# FPGA_1.net
KiCad netlist of a schematic drawn in Altium Designer
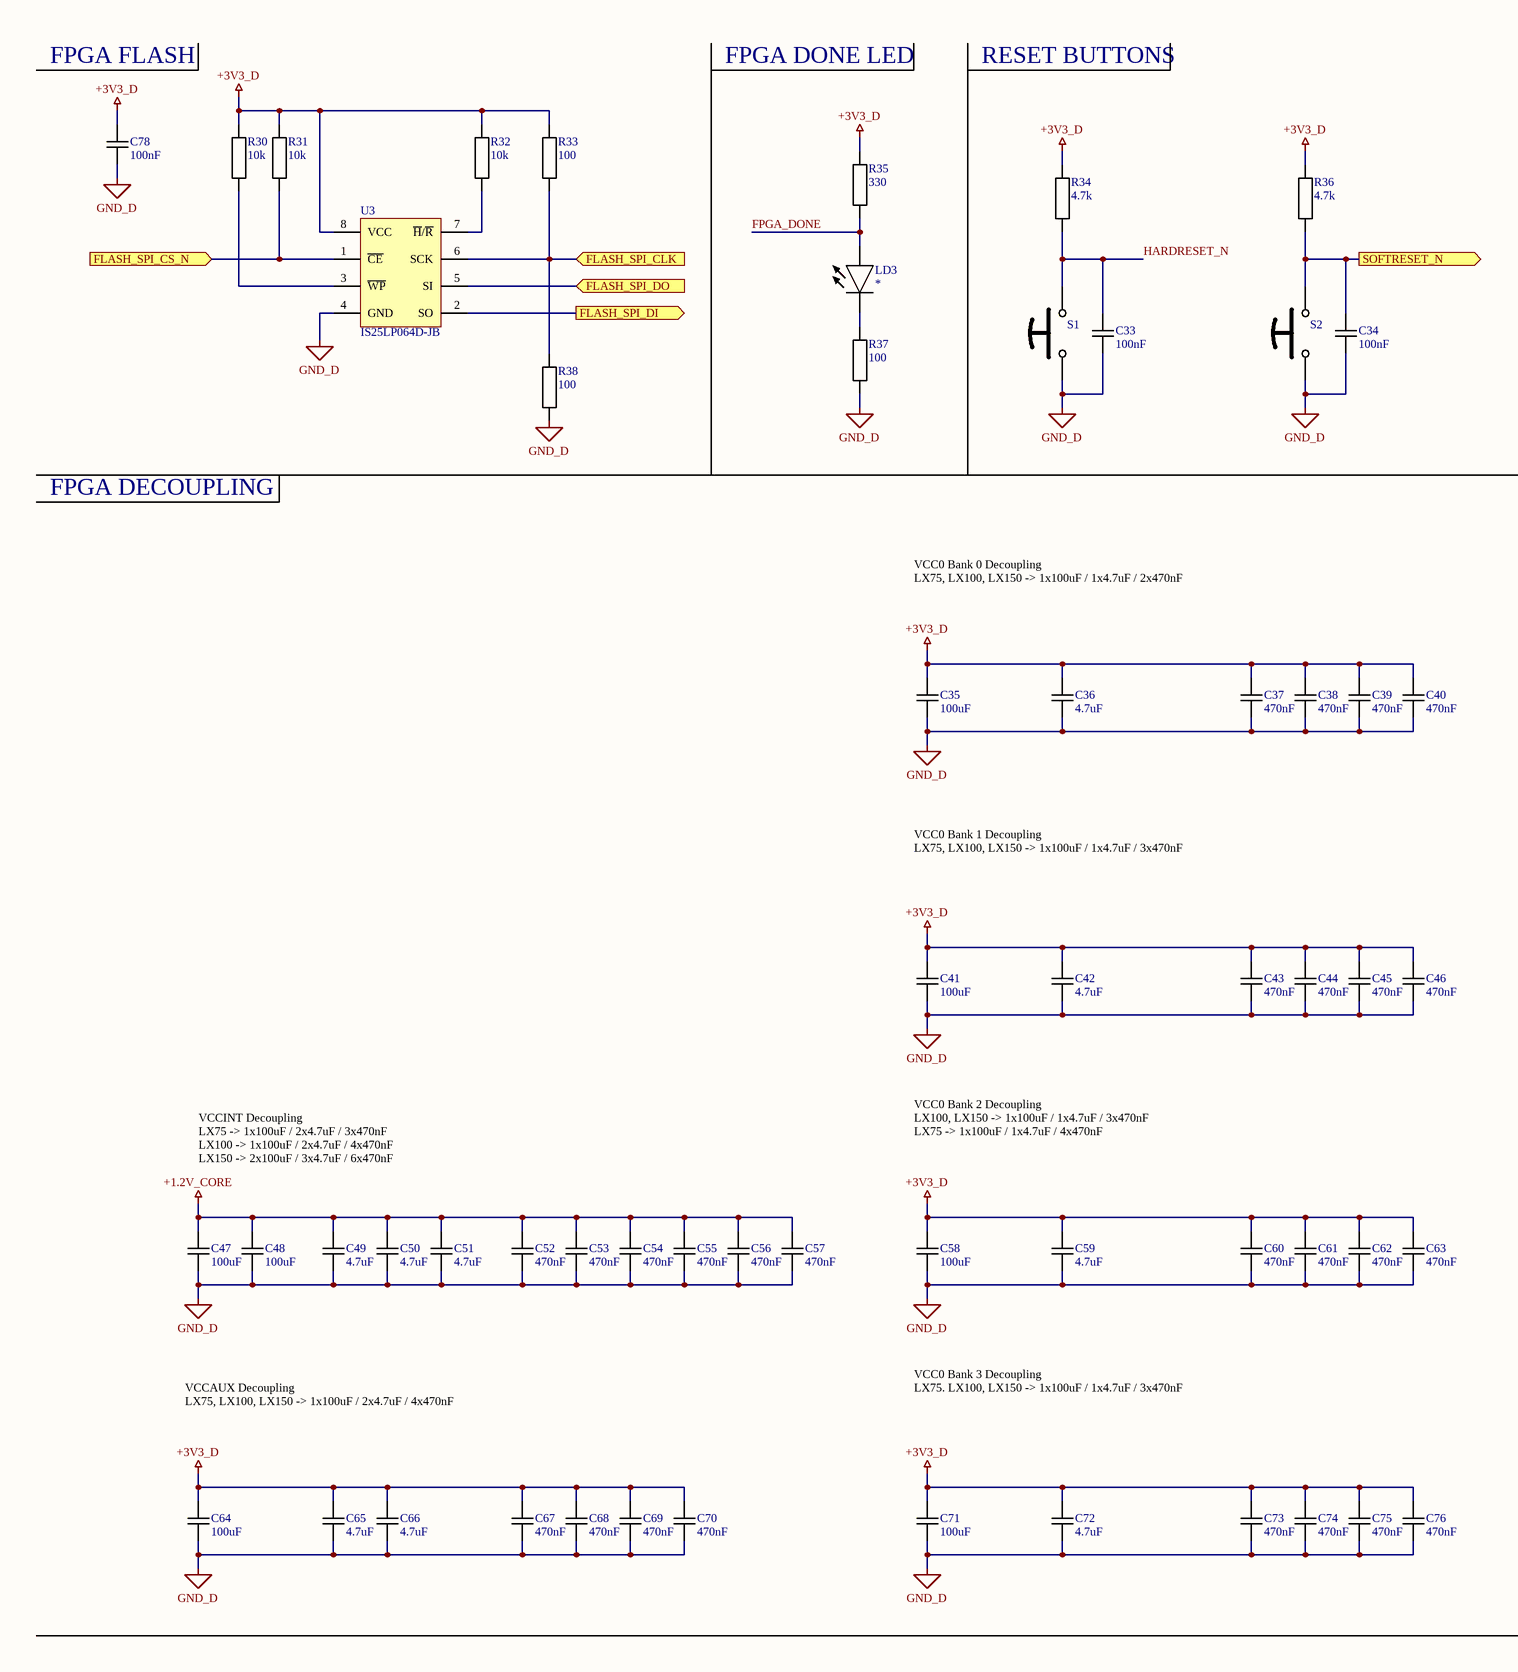
[diagram p0: FPGA_1.SchDoc, left]
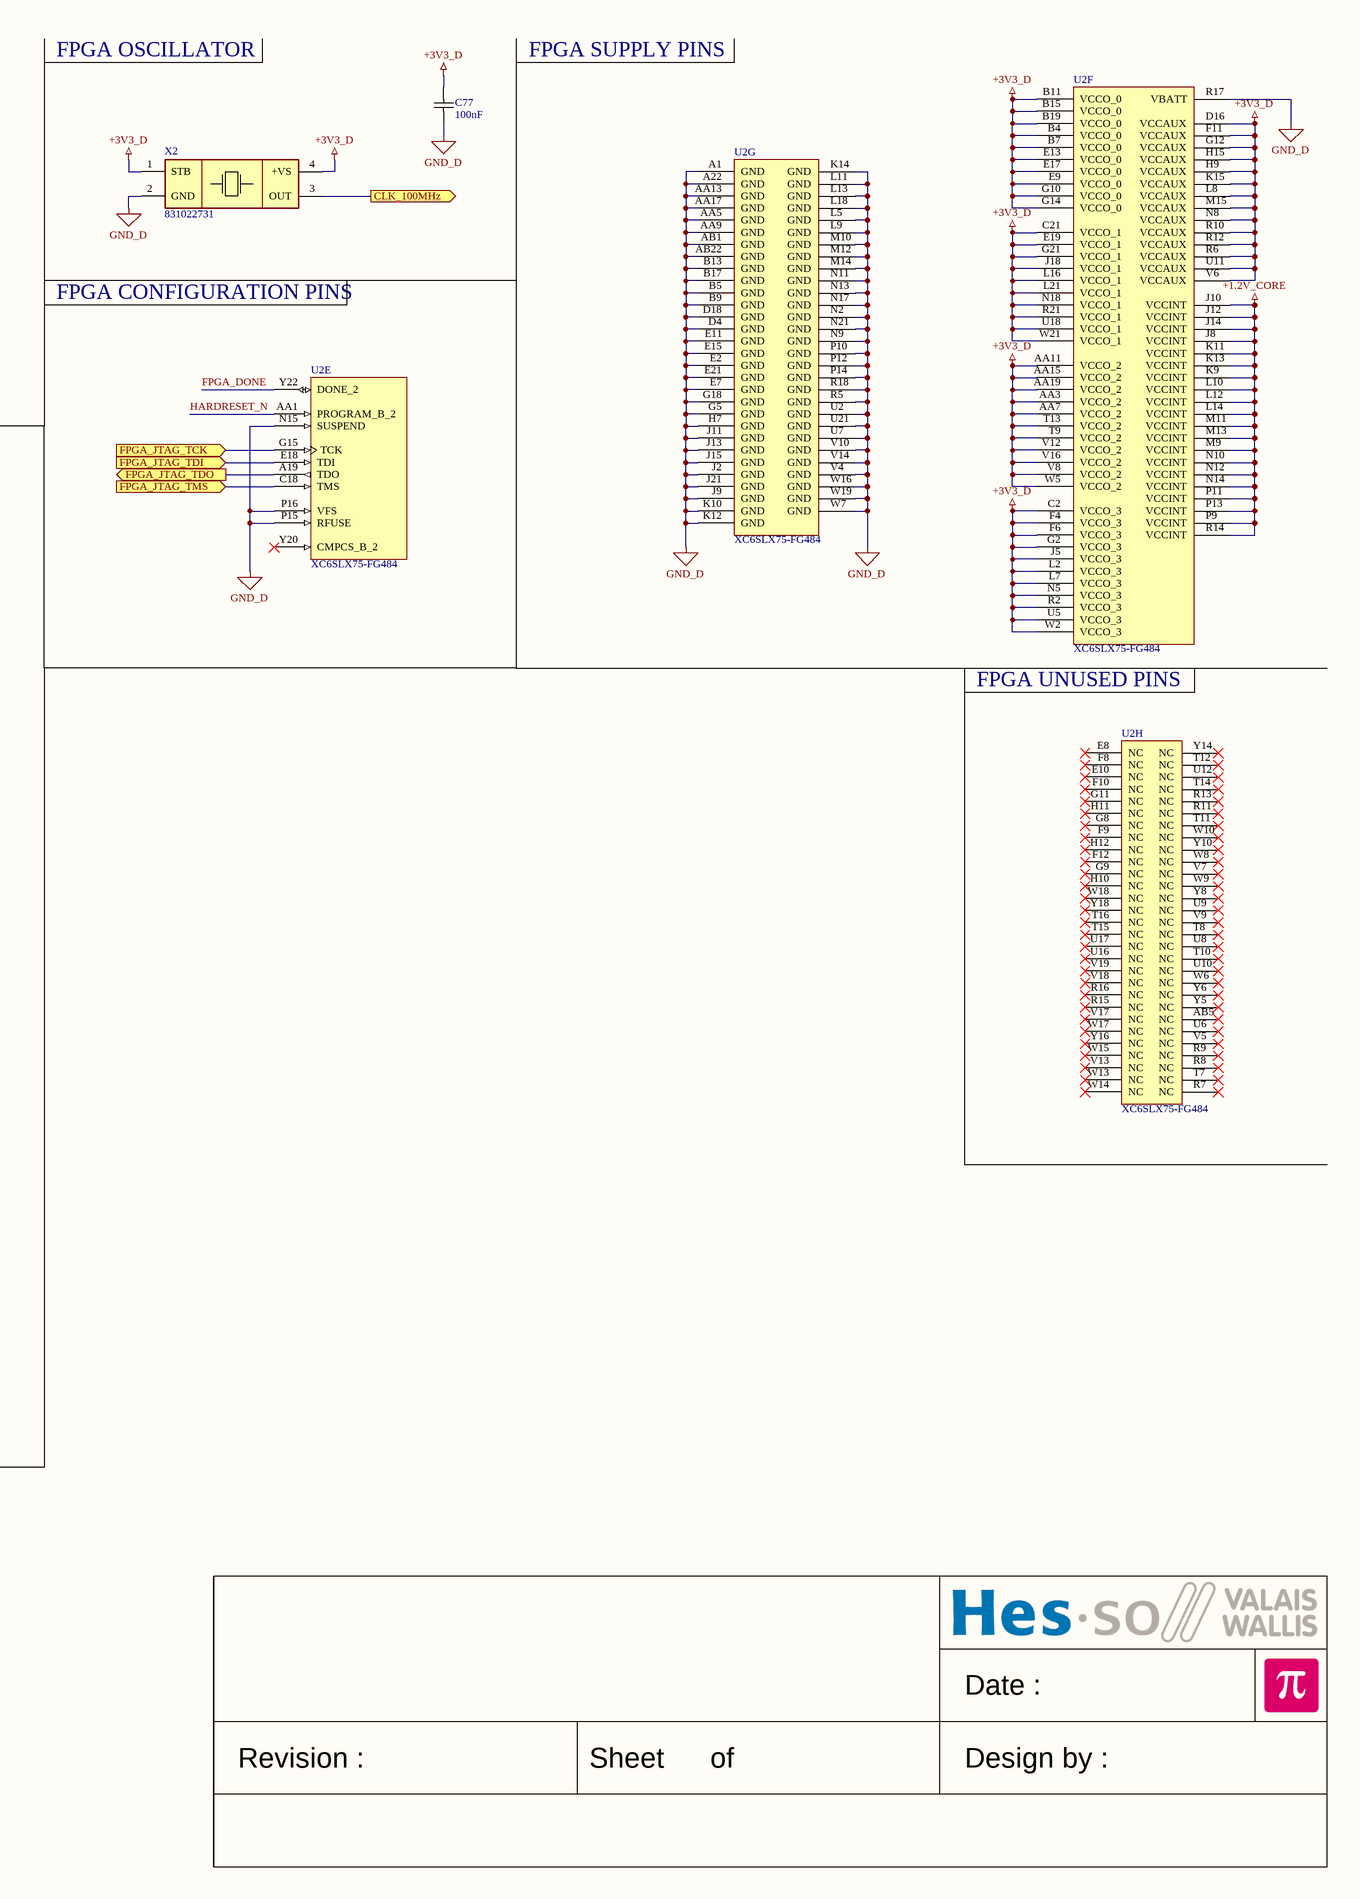
[diagram p1: FPGA_1.SchDoc, right]

(export (version "E")
  (design (tool "Eeschema 10.0.6"))
  (components
    (comp (ref "C33")
      (value "100nF")
      (footprint "CAPACITOR 1608 REFLOW")
      (description "Capacitor")
      (libsource (lib "Capacitor") (part "Capacitor"))
    )
    (comp (ref "C34")
      (value "100nF")
      (footprint "CAPACITOR 1608 REFLOW")
      (description "Capacitor")
      (libsource (lib "Capacitor") (part "Capacitor"))
    )
    (comp (ref "C35")
      (value "100uF")
      (footprint "CAPACITOR 3216 REFLOW")
      (description "Capacitor")
      (libsource (lib "Capacitor") (part "Capacitor"))
    )
    (comp (ref "C36")
      (value "4.7uF")
      (footprint "CAPACITOR 1608 REFLOW")
      (description "Capacitor")
      (libsource (lib "Capacitor") (part "Capacitor"))
    )
    (comp (ref "C37")
      (value "470nF")
      (footprint "CAPACITOR 1005 REFLOW")
      (description "Capacitor")
      (libsource (lib "Capacitor") (part "Capacitor"))
    )
    (comp (ref "C38")
      (value "470nF")
      (footprint "CAPACITOR 1005 REFLOW")
      (description "Capacitor")
      (libsource (lib "Capacitor") (part "Capacitor"))
    )
    (comp (ref "C39")
      (value "470nF")
      (footprint "CAPACITOR 1005 REFLOW")
      (description "Capacitor")
      (libsource (lib "Capacitor") (part "Capacitor"))
    )
    (comp (ref "C40")
      (value "470nF")
      (footprint "CAPACITOR 1005 REFLOW")
      (description "Capacitor")
      (libsource (lib "Capacitor") (part "Capacitor"))
    )
    (comp (ref "C41")
      (value "100uF")
      (footprint "CAPACITOR 3216 REFLOW")
      (description "Capacitor")
      (libsource (lib "Capacitor") (part "Capacitor"))
    )
    (comp (ref "C42")
      (value "4.7uF")
      (footprint "CAPACITOR 1608 REFLOW")
      (description "Capacitor")
      (libsource (lib "Capacitor") (part "Capacitor"))
    )
    (comp (ref "C43")
      (value "470nF")
      (footprint "CAPACITOR 1005 REFLOW")
      (description "Capacitor")
      (libsource (lib "Capacitor") (part "Capacitor"))
    )
    (comp (ref "C44")
      (value "470nF")
      (footprint "CAPACITOR 1005 REFLOW")
      (description "Capacitor")
      (libsource (lib "Capacitor") (part "Capacitor"))
    )
    (comp (ref "C45")
      (value "470nF")
      (footprint "CAPACITOR 1005 REFLOW")
      (description "Capacitor")
      (libsource (lib "Capacitor") (part "Capacitor"))
    )
    (comp (ref "C46")
      (value "470nF")
      (footprint "CAPACITOR 1005 REFLOW")
      (description "Capacitor")
      (libsource (lib "Capacitor") (part "Capacitor"))
    )
    (comp (ref "C47")
      (value "100uF")
      (footprint "CAPACITOR 3216 REFLOW")
      (description "Capacitor")
      (libsource (lib "Capacitor") (part "Capacitor"))
    )
    (comp (ref "C48")
      (value "100uF")
      (footprint "CAPACITOR 3216 REFLOW")
      (description "Capacitor")
      (libsource (lib "Capacitor") (part "Capacitor"))
    )
    (comp (ref "C49")
      (value "4.7uF")
      (footprint "CAPACITOR 1608 REFLOW")
      (description "Capacitor")
      (libsource (lib "Capacitor") (part "Capacitor"))
    )
    (comp (ref "C50")
      (value "4.7uF")
      (footprint "CAPACITOR 1608 REFLOW")
      (description "Capacitor")
      (libsource (lib "Capacitor") (part "Capacitor"))
    )
    (comp (ref "C51")
      (value "4.7uF")
      (footprint "CAPACITOR 1608 REFLOW")
      (description "Capacitor")
      (libsource (lib "Capacitor") (part "Capacitor"))
    )
    (comp (ref "C52")
      (value "470nF")
      (footprint "CAPACITOR 1005 REFLOW")
      (description "Capacitor")
      (libsource (lib "Capacitor") (part "Capacitor"))
    )
    (comp (ref "C53")
      (value "470nF")
      (footprint "CAPACITOR 1005 REFLOW")
      (description "Capacitor")
      (libsource (lib "Capacitor") (part "Capacitor"))
    )
    (comp (ref "C54")
      (value "470nF")
      (footprint "CAPACITOR 1005 REFLOW")
      (description "Capacitor")
      (libsource (lib "Capacitor") (part "Capacitor"))
    )
    (comp (ref "C55")
      (value "470nF")
      (footprint "CAPACITOR 1005 REFLOW")
      (description "Capacitor")
      (libsource (lib "Capacitor") (part "Capacitor"))
    )
    (comp (ref "C56")
      (value "470nF")
      (footprint "CAPACITOR 1005 REFLOW")
      (description "Capacitor")
      (libsource (lib "Capacitor") (part "Capacitor"))
    )
    (comp (ref "C57")
      (value "470nF")
      (footprint "CAPACITOR 1005 REFLOW")
      (description "Capacitor")
      (libsource (lib "Capacitor") (part "Capacitor"))
    )
    (comp (ref "C58")
      (value "100uF")
      (footprint "CAPACITOR 3216 REFLOW")
      (description "Capacitor")
      (libsource (lib "Capacitor") (part "Capacitor"))
    )
    (comp (ref "C59")
      (value "4.7uF")
      (footprint "CAPACITOR 1608 REFLOW")
      (description "Capacitor")
      (libsource (lib "Capacitor") (part "Capacitor"))
    )
    (comp (ref "C60")
      (value "470nF")
      (footprint "CAPACITOR 1005 REFLOW")
      (description "Capacitor")
      (libsource (lib "Capacitor") (part "Capacitor"))
    )
    (comp (ref "C61")
      (value "470nF")
      (footprint "CAPACITOR 1005 REFLOW")
      (description "Capacitor")
      (libsource (lib "Capacitor") (part "Capacitor"))
    )
    (comp (ref "C62")
      (value "470nF")
      (footprint "CAPACITOR 1005 REFLOW")
      (description "Capacitor")
      (libsource (lib "Capacitor") (part "Capacitor"))
    )
    (comp (ref "C63")
      (value "470nF")
      (footprint "CAPACITOR 1005 REFLOW")
      (description "Capacitor")
      (libsource (lib "Capacitor") (part "Capacitor"))
    )
    (comp (ref "C64")
      (value "100uF")
      (footprint "CAPACITOR 3216 REFLOW")
      (description "Capacitor")
      (libsource (lib "Capacitor") (part "Capacitor"))
    )
    (comp (ref "C65")
      (value "4.7uF")
      (footprint "CAPACITOR 1608 REFLOW")
      (description "Capacitor")
      (libsource (lib "Capacitor") (part "Capacitor"))
    )
    (comp (ref "C66")
      (value "4.7uF")
      (footprint "CAPACITOR 1608 REFLOW")
      (description "Capacitor")
      (libsource (lib "Capacitor") (part "Capacitor"))
    )
    (comp (ref "C67")
      (value "470nF")
      (footprint "CAPACITOR 1005 REFLOW")
      (description "Capacitor")
      (libsource (lib "Capacitor") (part "Capacitor"))
    )
    (comp (ref "C68")
      (value "470nF")
      (footprint "CAPACITOR 1005 REFLOW")
      (description "Capacitor")
      (libsource (lib "Capacitor") (part "Capacitor"))
    )
    (comp (ref "C69")
      (value "470nF")
      (footprint "CAPACITOR 1005 REFLOW")
      (description "Capacitor")
      (libsource (lib "Capacitor") (part "Capacitor"))
    )
    (comp (ref "C70")
      (value "470nF")
      (footprint "CAPACITOR 1005 REFLOW")
      (description "Capacitor")
      (libsource (lib "Capacitor") (part "Capacitor"))
    )
    (comp (ref "C71")
      (value "100uF")
      (footprint "CAPACITOR 3216 REFLOW")
      (description "Capacitor")
      (libsource (lib "Capacitor") (part "Capacitor"))
    )
    (comp (ref "C72")
      (value "4.7uF")
      (footprint "CAPACITOR 1608 REFLOW")
      (description "Capacitor")
      (libsource (lib "Capacitor") (part "Capacitor"))
    )
    (comp (ref "C73")
      (value "470nF")
      (footprint "CAPACITOR 1005 REFLOW")
      (description "Capacitor")
      (libsource (lib "Capacitor") (part "Capacitor"))
    )
    (comp (ref "C74")
      (value "470nF")
      (footprint "CAPACITOR 1005 REFLOW")
      (description "Capacitor")
      (libsource (lib "Capacitor") (part "Capacitor"))
    )
    (comp (ref "C75")
      (value "470nF")
      (footprint "CAPACITOR 1005 REFLOW")
      (description "Capacitor")
      (libsource (lib "Capacitor") (part "Capacitor"))
    )
    (comp (ref "C76")
      (value "470nF")
      (footprint "CAPACITOR 1005 REFLOW")
      (description "Capacitor")
      (libsource (lib "Capacitor") (part "Capacitor"))
    )
    (comp (ref "C77")
      (value "100nF")
      (footprint "CAPACITOR 1608 REFLOW")
      (description "Capacitor")
      (libsource (lib "Capacitor") (part "Capacitor"))
    )
    (comp (ref "C78")
      (value "100nF")
      (footprint "CAPACITOR 1608 REFLOW")
      (description "Capacitor")
      (libsource (lib "Capacitor") (part "Capacitor"))
    )
    (comp (ref "LD3")
      (value "*")
      (footprint "LED 1608 REFLOW")
      (description "LED generic")
      (libsource (lib "Diode") (part "LED"))
    )
    (comp (ref "R30")
      (value "10k")
      (footprint "RESISTOR 1608 REFLOW")
      (description "Resistor 1% 50V 100mW 1608(0603)")
      (libsource (lib "Resistor") (part "Resistor"))
    )
    (comp (ref "R31")
      (value "10k")
      (footprint "RESISTOR 1608 REFLOW")
      (description "Resistor 1% 50V 100mW 1608(0603)")
      (libsource (lib "Resistor") (part "Resistor"))
    )
    (comp (ref "R32")
      (value "10k")
      (footprint "RESISTOR 1608 REFLOW")
      (description "Resistor 1% 50V 100mW 1608(0603)")
      (libsource (lib "Resistor") (part "Resistor"))
    )
    (comp (ref "R33")
      (value "100")
      (footprint "RESISTOR 1608 REFLOW")
      (description "Resistor 1% 50V 100mW 1608(0603)")
      (libsource (lib "Resistor") (part "Resistor"))
    )
    (comp (ref "R34")
      (value "4.7k")
      (footprint "RESISTOR 1608 REFLOW")
      (description "Resistor 1% 50V 125mW 2012(0805)")
      (libsource (lib "Resistor") (part "Resistor"))
    )
    (comp (ref "R35")
      (value "330")
      (footprint "RESISTOR 1608 REFLOW")
      (description "Resistor 1% 50V 125mW 2012(0805)")
      (libsource (lib "Resistor") (part "Resistor"))
    )
    (comp (ref "R36")
      (value "4.7k")
      (footprint "RESISTOR 1608 REFLOW")
      (description "Resistor 1% 50V 125mW 2012(0805)")
      (libsource (lib "Resistor") (part "Resistor"))
    )
    (comp (ref "R37")
      (value "100")
      (footprint "RESISTOR 1608 REFLOW")
      (description "Resistor 1% 50V 125mW 2012(0805)")
      (libsource (lib "Resistor") (part "Resistor"))
    )
    (comp (ref "R38")
      (value "100")
      (footprint "RESISTOR 1608 REFLOW")
      (description "Resistor 1% 50V 100mW 1608(0603)")
      (libsource (lib "Resistor") (part "Resistor"))
    )
    (comp (ref "S1")
      (value "*")
      (footprint "Push Button C6.0x3.5 Tyco FSMSM")
      (description "Push Button, 2 pins")
      (libsource (lib "Button") (part "Push Button 2Pins"))
    )
    (comp (ref "S2")
      (value "*")
      (footprint "Push Button C6.0x3.5 Tyco FSMSM")
      (description "Push Button, 2 pins")
      (libsource (lib "Button") (part "Push Button 2Pins"))
    )
    (comp (ref "U2")
      (value "XC6SLX75-FG484")
      (footprint "BGA484 P1.0 C23X23 H2.2")
      (description "Spartan-6 LXT 1.2V FPGA, 268 User I/Os, 484-Ball Fine-Pitch BGA (1.0mm Pitch)")
      (libsource (lib "Processor") (part "XC6SLX75-FG484"))
    )
    (comp (ref "U3")
      (value "IS25LP064D-JB")
      (footprint "SO8 P1.27 C4.0X5.0 H1.75")
      (description "64Mb Serial Flash Memory")
      (libsource (lib "Memory") (part "IS25LP064D-JB"))
    )
    (comp (ref "X2")
      (value "831022731")
      (footprint "Oscillator C5.2x7.2 IQD LFSPXO")
      (description "Oscillator C5.2x7.2 IQD LFSPXO")
      (libsource (lib "Oscillator") (part "Oscillator C5.2x7.2 IQD LFSPXO"))
    )
  )
  (nets
    (net (code "1") (name "+1.2V_CORE") (class "Default")
      (node (ref "C47") (pin "1") (pinfunction "1_1") (pintype "passive"))
      (node (ref "C48") (pin "1") (pinfunction "1_1") (pintype "passive"))
      (node (ref "C49") (pin "1") (pinfunction "1_1") (pintype "passive"))
      (node (ref "C50") (pin "1") (pinfunction "1_1") (pintype "passive"))
      (node (ref "C51") (pin "1") (pinfunction "1_1") (pintype "passive"))
      (node (ref "C52") (pin "1") (pinfunction "1_1") (pintype "passive"))
      (node (ref "C53") (pin "1") (pinfunction "1_1") (pintype "passive"))
      (node (ref "C54") (pin "1") (pinfunction "1_1") (pintype "passive"))
      (node (ref "C55") (pin "1") (pinfunction "1_1") (pintype "passive"))
      (node (ref "C56") (pin "1") (pinfunction "1_1") (pintype "passive"))
      (node (ref "C57") (pin "1") (pinfunction "1_1") (pintype "passive"))
      (node (ref "U2") (pin "J10") (pinfunction "VCCINT_J10") (pintype "power_in"))
      (node (ref "U2") (pin "J12") (pinfunction "VCCINT_J12") (pintype "power_in"))
      (node (ref "U2") (pin "J14") (pinfunction "VCCINT_J14") (pintype "power_in"))
      (node (ref "U2") (pin "J8") (pinfunction "VCCINT_J8") (pintype "power_in"))
      (node (ref "U2") (pin "K11") (pinfunction "VCCINT_K11") (pintype "power_in"))
      (node (ref "U2") (pin "K13") (pinfunction "VCCINT_K13") (pintype "power_in"))
      (node (ref "U2") (pin "K9") (pinfunction "VCCINT_K9") (pintype "power_in"))
      (node (ref "U2") (pin "L10") (pinfunction "VCCINT_L10") (pintype "power_in"))
      (node (ref "U2") (pin "L12") (pinfunction "VCCINT_L12") (pintype "power_in"))
      (node (ref "U2") (pin "L14") (pinfunction "VCCINT_L14") (pintype "power_in"))
      (node (ref "U2") (pin "M11") (pinfunction "VCCINT_M11") (pintype "power_in"))
      (node (ref "U2") (pin "M13") (pinfunction "VCCINT_M13") (pintype "power_in"))
      (node (ref "U2") (pin "M9") (pinfunction "VCCINT_M9") (pintype "power_in"))
      (node (ref "U2") (pin "N10") (pinfunction "VCCINT_N10") (pintype "power_in"))
      (node (ref "U2") (pin "N12") (pinfunction "VCCINT_N12") (pintype "power_in"))
      (node (ref "U2") (pin "N14") (pinfunction "VCCINT_N14") (pintype "power_in"))
      (node (ref "U2") (pin "P11") (pinfunction "VCCINT_P11") (pintype "power_in"))
      (node (ref "U2") (pin "P13") (pinfunction "VCCINT_P13") (pintype "power_in"))
      (node (ref "U2") (pin "P9") (pinfunction "VCCINT_P9") (pintype "power_in"))
      (node (ref "U2") (pin "R14") (pinfunction "VCCINT_R14") (pintype "power_in"))
    )
    (net (code "2") (name "+3V3_D") (class "Default")
      (node (ref "C35") (pin "1") (pinfunction "1_1") (pintype "passive"))
      (node (ref "C36") (pin "1") (pinfunction "1_1") (pintype "passive"))
      (node (ref "C37") (pin "1") (pinfunction "1_1") (pintype "passive"))
      (node (ref "C38") (pin "1") (pinfunction "1_1") (pintype "passive"))
      (node (ref "C39") (pin "1") (pinfunction "1_1") (pintype "passive"))
      (node (ref "C40") (pin "1") (pinfunction "1_1") (pintype "passive"))
      (node (ref "C41") (pin "1") (pinfunction "1_1") (pintype "passive"))
      (node (ref "C42") (pin "1") (pinfunction "1_1") (pintype "passive"))
      (node (ref "C43") (pin "1") (pinfunction "1_1") (pintype "passive"))
      (node (ref "C44") (pin "1") (pinfunction "1_1") (pintype "passive"))
      (node (ref "C45") (pin "1") (pinfunction "1_1") (pintype "passive"))
      (node (ref "C46") (pin "1") (pinfunction "1_1") (pintype "passive"))
      (node (ref "C58") (pin "1") (pinfunction "1_1") (pintype "passive"))
      (node (ref "C59") (pin "1") (pinfunction "1_1") (pintype "passive"))
      (node (ref "C60") (pin "1") (pinfunction "1_1") (pintype "passive"))
      (node (ref "C61") (pin "1") (pinfunction "1_1") (pintype "passive"))
      (node (ref "C62") (pin "1") (pinfunction "1_1") (pintype "passive"))
      (node (ref "C63") (pin "1") (pinfunction "1_1") (pintype "passive"))
      (node (ref "C64") (pin "1") (pinfunction "1_1") (pintype "passive"))
      (node (ref "C65") (pin "1") (pinfunction "1_1") (pintype "passive"))
      (node (ref "C66") (pin "1") (pinfunction "1_1") (pintype "passive"))
      (node (ref "C67") (pin "1") (pinfunction "1_1") (pintype "passive"))
      (node (ref "C68") (pin "1") (pinfunction "1_1") (pintype "passive"))
      (node (ref "C69") (pin "1") (pinfunction "1_1") (pintype "passive"))
      (node (ref "C70") (pin "1") (pinfunction "1_1") (pintype "passive"))
      (node (ref "C71") (pin "1") (pinfunction "1_1") (pintype "passive"))
      (node (ref "C72") (pin "1") (pinfunction "1_1") (pintype "passive"))
      (node (ref "C73") (pin "1") (pinfunction "1_1") (pintype "passive"))
      (node (ref "C74") (pin "1") (pinfunction "1_1") (pintype "passive"))
      (node (ref "C75") (pin "1") (pinfunction "1_1") (pintype "passive"))
      (node (ref "C76") (pin "1") (pinfunction "1_1") (pintype "passive"))
      (node (ref "C77") (pin "2") (pinfunction "2_2") (pintype "passive"))
      (node (ref "C78") (pin "2") (pinfunction "2_2") (pintype "passive"))
      (node (ref "R30") (pin "2") (pinfunction "2_2") (pintype "passive"))
      (node (ref "R31") (pin "2") (pinfunction "2_2") (pintype "passive"))
      (node (ref "R32") (pin "2") (pinfunction "2_2") (pintype "passive"))
      (node (ref "R33") (pin "2") (pinfunction "2_2") (pintype "passive"))
      (node (ref "R34") (pin "2") (pinfunction "2_2") (pintype "passive"))
      (node (ref "R35") (pin "2") (pinfunction "2_2") (pintype "passive"))
      (node (ref "R36") (pin "2") (pinfunction "2_2") (pintype "passive"))
      (node (ref "U2") (pin "AA11") (pinfunction "VCCO_2_AA11") (pintype "power_in"))
      (node (ref "U2") (pin "AA15") (pinfunction "VCCO_2_AA15") (pintype "power_in"))
      (node (ref "U2") (pin "AA19") (pinfunction "VCCO_2_AA19") (pintype "power_in"))
      (node (ref "U2") (pin "AA3") (pinfunction "VCCO_2_AA3") (pintype "power_in"))
      (node (ref "U2") (pin "AA7") (pinfunction "VCCO_2_AA7") (pintype "power_in"))
      (node (ref "U2") (pin "B11") (pinfunction "VCCO_0_B11") (pintype "power_in"))
      (node (ref "U2") (pin "B15") (pinfunction "VCCO_0_B15") (pintype "power_in"))
      (node (ref "U2") (pin "B19") (pinfunction "VCCO_0_B19") (pintype "power_in"))
      (node (ref "U2") (pin "B4") (pinfunction "VCCO_0_B4") (pintype "power_in"))
      (node (ref "U2") (pin "B7") (pinfunction "VCCO_0_B7") (pintype "power_in"))
      (node (ref "U2") (pin "C2") (pinfunction "VCCO_3_C2") (pintype "power_in"))
      (node (ref "U2") (pin "C21") (pinfunction "VCCO_1_C21") (pintype "power_in"))
      (node (ref "U2") (pin "D16") (pinfunction "VCCAUX_D16") (pintype "power_in"))
      (node (ref "U2") (pin "E13") (pinfunction "VCCO_0_E13") (pintype "power_in"))
      (node (ref "U2") (pin "E17") (pinfunction "VCCO_0_E17") (pintype "power_in"))
      (node (ref "U2") (pin "E19") (pinfunction "VCCO_1_E19") (pintype "power_in"))
      (node (ref "U2") (pin "E9") (pinfunction "VCCO_0_E9") (pintype "power_in"))
      (node (ref "U2") (pin "F11") (pinfunction "VCCAUX_F11") (pintype "power_in"))
      (node (ref "U2") (pin "F4") (pinfunction "VCCO_3_F4") (pintype "power_in"))
      (node (ref "U2") (pin "F6") (pinfunction "VCCO_3_F6") (pintype "power_in"))
      (node (ref "U2") (pin "G10") (pinfunction "VCCO_0_G10") (pintype "power_in"))
      (node (ref "U2") (pin "G12") (pinfunction "VCCAUX_G12") (pintype "power_in"))
      (node (ref "U2") (pin "G14") (pinfunction "VCCO_0_G14") (pintype "power_in"))
      (node (ref "U2") (pin "G2") (pinfunction "VCCO_3_G2") (pintype "power_in"))
      (node (ref "U2") (pin "G21") (pinfunction "VCCO_1_G21") (pintype "power_in"))
      (node (ref "U2") (pin "H15") (pinfunction "VCCAUX_H15") (pintype "power_in"))
      (node (ref "U2") (pin "H9") (pinfunction "VCCAUX_H9") (pintype "power_in"))
      (node (ref "U2") (pin "J18") (pinfunction "VCCO_1_J18") (pintype "power_in"))
      (node (ref "U2") (pin "J5") (pinfunction "VCCO_3_J5") (pintype "power_in"))
      (node (ref "U2") (pin "K15") (pinfunction "VCCAUX_K15") (pintype "power_in"))
      (node (ref "U2") (pin "L16") (pinfunction "VCCO_1_L16") (pintype "power_in"))
      (node (ref "U2") (pin "L2") (pinfunction "VCCO_3_L2") (pintype "power_in"))
      (node (ref "U2") (pin "L21") (pinfunction "VCCO_1_L21") (pintype "power_in"))
      (node (ref "U2") (pin "L7") (pinfunction "VCCO_3_L7") (pintype "power_in"))
      (node (ref "U2") (pin "L8") (pinfunction "VCCAUX_L8") (pintype "power_in"))
      (node (ref "U2") (pin "M15") (pinfunction "VCCAUX_M15") (pintype "power_in"))
      (node (ref "U2") (pin "N18") (pinfunction "VCCO_1_N18") (pintype "power_in"))
      (node (ref "U2") (pin "N5") (pinfunction "VCCO_3_N5") (pintype "power_in"))
      (node (ref "U2") (pin "N8") (pinfunction "VCCAUX_N8") (pintype "power_in"))
      (node (ref "U2") (pin "R10") (pinfunction "VCCAUX_R10") (pintype "power_in"))
      (node (ref "U2") (pin "R12") (pinfunction "VCCAUX_R12") (pintype "power_in"))
      (node (ref "U2") (pin "R2") (pinfunction "VCCO_3_R2") (pintype "power_in"))
      (node (ref "U2") (pin "R21") (pinfunction "VCCO_1_R21") (pintype "power_in"))
      (node (ref "U2") (pin "R6") (pinfunction "VCCAUX_R6") (pintype "power_in"))
      (node (ref "U2") (pin "T13") (pinfunction "VCCO_2_T13") (pintype "power_in"))
      (node (ref "U2") (pin "T9") (pinfunction "VCCO_2_T9") (pintype "power_in"))
      (node (ref "U2") (pin "U11") (pinfunction "VCCAUX_U11") (pintype "power_in"))
      (node (ref "U2") (pin "U18") (pinfunction "VCCO_1_U18") (pintype "power_in"))
      (node (ref "U2") (pin "U5") (pinfunction "VCCO_3_U5") (pintype "power_in"))
      (node (ref "U2") (pin "V12") (pinfunction "VCCO_2_V12") (pintype "power_in"))
      (node (ref "U2") (pin "V16") (pinfunction "VCCO_2_V16") (pintype "power_in"))
      (node (ref "U2") (pin "V6") (pinfunction "VCCAUX_V6") (pintype "power_in"))
      (node (ref "U2") (pin "V8") (pinfunction "VCCO_2_V8") (pintype "power_in"))
      (node (ref "U2") (pin "W2") (pinfunction "VCCO_3_W2") (pintype "power_in"))
      (node (ref "U2") (pin "W21") (pinfunction "VCCO_1_W21") (pintype "power_in"))
      (node (ref "U2") (pin "W5") (pinfunction "VCCO_2_W5") (pintype "power_in"))
      (node (ref "U3") (pin "8") (pinfunction "VCC_8") (pintype "power_in"))
      (node (ref "X2") (pin "1") (pinfunction "STB_1") (pintype "passive"))
      (node (ref "X2") (pin "4") (pinfunction "+VS_4") (pintype "passive"))
    )
    (net (code "3") (name "/CLK_100MHz") (class "Default")
      (node (ref "X2") (pin "3") (pinfunction "OUT_3") (pintype "passive"))
    )
    (net (code "4") (name "/FLASH_SPI_CLK") (class "Default")
      (node (ref "R33") (pin "1") (pinfunction "1_1") (pintype "passive"))
      (node (ref "R38") (pin "2") (pinfunction "2_2") (pintype "passive"))
      (node (ref "U3") (pin "6") (pinfunction "SCK_6") (pintype "passive"))
    )
    (net (code "5") (name "/FLASH_SPI_CS_N") (class "Default")
      (node (ref "R31") (pin "1") (pinfunction "1_1") (pintype "passive"))
      (node (ref "U3") (pin "1") (pinfunction "~{CE}_1") (pintype "passive"))
    )
    (net (code "6") (name "/FLASH_SPI_DI") (class "Default")
      (node (ref "U3") (pin "2") (pinfunction "SO_2") (pintype "passive"))
    )
    (net (code "7") (name "/FLASH_SPI_DO") (class "Default")
      (node (ref "U3") (pin "5") (pinfunction "SI_5") (pintype "passive"))
    )
    (net (code "8") (name "/FPGA_DONE") (class "Default")
      (node (ref "LD3") (pin "2") (pinfunction "A_2") (pintype "passive"))
      (node (ref "R35") (pin "1") (pinfunction "1_1") (pintype "passive"))
      (node (ref "U2") (pin "Y22") (pinfunction "DONE_2_Y22") (pintype "bidirectional"))
    )
    (net (code "9") (name "/FPGA_JTAG_TCK") (class "Default")
      (node (ref "U2") (pin "G15") (pinfunction "TCK_G15") (pintype "input"))
    )
    (net (code "10") (name "/FPGA_JTAG_TDI") (class "Default")
      (node (ref "U2") (pin "E18") (pinfunction "TDI_E18") (pintype "input"))
    )
    (net (code "11") (name "/FPGA_JTAG_TDO") (class "Default")
      (node (ref "U2") (pin "A19") (pinfunction "TDO_A19") (pintype "output"))
    )
    (net (code "12") (name "/FPGA_JTAG_TMS") (class "Default")
      (node (ref "U2") (pin "C18") (pinfunction "TMS_C18") (pintype "input"))
    )
    (net (code "13") (name "/HARDRESET_N") (class "Default")
      (node (ref "C33") (pin "2") (pinfunction "2_2") (pintype "passive"))
      (node (ref "R34") (pin "1") (pinfunction "1_1") (pintype "passive"))
      (node (ref "S1") (pin "2") (pinfunction "2_2") (pintype "passive"))
      (node (ref "U2") (pin "AA1") (pinfunction "PROGRAM_B_2_AA1") (pintype "input"))
    )
    (net (code "14") (name "/SOFTRESET_N") (class "Default")
      (node (ref "C34") (pin "2") (pinfunction "2_2") (pintype "passive"))
      (node (ref "R36") (pin "1") (pinfunction "1_1") (pintype "passive"))
      (node (ref "S2") (pin "2") (pinfunction "2_2") (pintype "passive"))
    )
    (net (code "15") (name "GND_D") (class "Default")
      (node (ref "C33") (pin "1") (pinfunction "1_1") (pintype "passive"))
      (node (ref "C34") (pin "1") (pinfunction "1_1") (pintype "passive"))
      (node (ref "C35") (pin "2") (pinfunction "2_2") (pintype "passive"))
      (node (ref "C36") (pin "2") (pinfunction "2_2") (pintype "passive"))
      (node (ref "C37") (pin "2") (pinfunction "2_2") (pintype "passive"))
      (node (ref "C38") (pin "2") (pinfunction "2_2") (pintype "passive"))
      (node (ref "C39") (pin "2") (pinfunction "2_2") (pintype "passive"))
      (node (ref "C40") (pin "2") (pinfunction "2_2") (pintype "passive"))
      (node (ref "C41") (pin "2") (pinfunction "2_2") (pintype "passive"))
      (node (ref "C42") (pin "2") (pinfunction "2_2") (pintype "passive"))
      (node (ref "C43") (pin "2") (pinfunction "2_2") (pintype "passive"))
      (node (ref "C44") (pin "2") (pinfunction "2_2") (pintype "passive"))
      (node (ref "C45") (pin "2") (pinfunction "2_2") (pintype "passive"))
      (node (ref "C46") (pin "2") (pinfunction "2_2") (pintype "passive"))
      (node (ref "C47") (pin "2") (pinfunction "2_2") (pintype "passive"))
      (node (ref "C48") (pin "2") (pinfunction "2_2") (pintype "passive"))
      (node (ref "C49") (pin "2") (pinfunction "2_2") (pintype "passive"))
      (node (ref "C50") (pin "2") (pinfunction "2_2") (pintype "passive"))
      (node (ref "C51") (pin "2") (pinfunction "2_2") (pintype "passive"))
      (node (ref "C52") (pin "2") (pinfunction "2_2") (pintype "passive"))
      (node (ref "C53") (pin "2") (pinfunction "2_2") (pintype "passive"))
      (node (ref "C54") (pin "2") (pinfunction "2_2") (pintype "passive"))
      (node (ref "C55") (pin "2") (pinfunction "2_2") (pintype "passive"))
      (node (ref "C56") (pin "2") (pinfunction "2_2") (pintype "passive"))
      (node (ref "C57") (pin "2") (pinfunction "2_2") (pintype "passive"))
      (node (ref "C58") (pin "2") (pinfunction "2_2") (pintype "passive"))
      (node (ref "C59") (pin "2") (pinfunction "2_2") (pintype "passive"))
      (node (ref "C60") (pin "2") (pinfunction "2_2") (pintype "passive"))
      (node (ref "C61") (pin "2") (pinfunction "2_2") (pintype "passive"))
      (node (ref "C62") (pin "2") (pinfunction "2_2") (pintype "passive"))
      (node (ref "C63") (pin "2") (pinfunction "2_2") (pintype "passive"))
      (node (ref "C64") (pin "2") (pinfunction "2_2") (pintype "passive"))
      (node (ref "C65") (pin "2") (pinfunction "2_2") (pintype "passive"))
      (node (ref "C66") (pin "2") (pinfunction "2_2") (pintype "passive"))
      (node (ref "C67") (pin "2") (pinfunction "2_2") (pintype "passive"))
      (node (ref "C68") (pin "2") (pinfunction "2_2") (pintype "passive"))
      (node (ref "C69") (pin "2") (pinfunction "2_2") (pintype "passive"))
      (node (ref "C70") (pin "2") (pinfunction "2_2") (pintype "passive"))
      (node (ref "C71") (pin "2") (pinfunction "2_2") (pintype "passive"))
      (node (ref "C72") (pin "2") (pinfunction "2_2") (pintype "passive"))
      (node (ref "C73") (pin "2") (pinfunction "2_2") (pintype "passive"))
      (node (ref "C74") (pin "2") (pinfunction "2_2") (pintype "passive"))
      (node (ref "C75") (pin "2") (pinfunction "2_2") (pintype "passive"))
      (node (ref "C76") (pin "2") (pinfunction "2_2") (pintype "passive"))
      (node (ref "C77") (pin "1") (pinfunction "1_1") (pintype "passive"))
      (node (ref "C78") (pin "1") (pinfunction "1_1") (pintype "passive"))
      (node (ref "R37") (pin "1") (pinfunction "1_1") (pintype "passive"))
      (node (ref "R38") (pin "1") (pinfunction "1_1") (pintype "passive"))
      (node (ref "S1") (pin "1") (pinfunction "1_1") (pintype "passive"))
      (node (ref "S2") (pin "1") (pinfunction "1_1") (pintype "passive"))
      (node (ref "U2") (pin "A1") (pinfunction "GND_A1") (pintype "power_in"))
      (node (ref "U2") (pin "A22") (pinfunction "GND_A22") (pintype "power_in"))
      (node (ref "U2") (pin "AA13") (pinfunction "GND_AA13") (pintype "power_in"))
      (node (ref "U2") (pin "AA17") (pinfunction "GND_AA17") (pintype "power_in"))
      (node (ref "U2") (pin "AA5") (pinfunction "GND_AA5") (pintype "power_in"))
      (node (ref "U2") (pin "AA9") (pinfunction "GND_AA9") (pintype "power_in"))
      (node (ref "U2") (pin "AB1") (pinfunction "GND_AB1") (pintype "power_in"))
      (node (ref "U2") (pin "AB22") (pinfunction "GND_AB22") (pintype "power_in"))
      (node (ref "U2") (pin "B13") (pinfunction "GND_B13") (pintype "power_in"))
      (node (ref "U2") (pin "B17") (pinfunction "GND_B17") (pintype "power_in"))
      (node (ref "U2") (pin "B5") (pinfunction "GND_B5") (pintype "power_in"))
      (node (ref "U2") (pin "B9") (pinfunction "GND_B9") (pintype "power_in"))
      (node (ref "U2") (pin "D18") (pinfunction "GND_D18") (pintype "power_in"))
      (node (ref "U2") (pin "D4") (pinfunction "GND_D4") (pintype "power_in"))
      (node (ref "U2") (pin "E11") (pinfunction "GND_E11") (pintype "power_in"))
      (node (ref "U2") (pin "E15") (pinfunction "GND_E15") (pintype "power_in"))
      (node (ref "U2") (pin "E2") (pinfunction "GND_E2") (pintype "power_in"))
      (node (ref "U2") (pin "E21") (pinfunction "GND_E21") (pintype "power_in"))
      (node (ref "U2") (pin "E7") (pinfunction "GND_E7") (pintype "power_in"))
      (node (ref "U2") (pin "G18") (pinfunction "GND_G18") (pintype "power_in"))
      (node (ref "U2") (pin "G5") (pinfunction "GND_G5") (pintype "power_in"))
      (node (ref "U2") (pin "H7") (pinfunction "GND_H7") (pintype "power_in"))
      (node (ref "U2") (pin "J11") (pinfunction "GND_J11") (pintype "power_in"))
      (node (ref "U2") (pin "J13") (pinfunction "GND_J13") (pintype "power_in"))
      (node (ref "U2") (pin "J15") (pinfunction "GND_J15") (pintype "power_in"))
      (node (ref "U2") (pin "J2") (pinfunction "GND_J2") (pintype "power_in"))
      (node (ref "U2") (pin "J21") (pinfunction "GND_J21") (pintype "power_in"))
      (node (ref "U2") (pin "J9") (pinfunction "GND_J9") (pintype "power_in"))
      (node (ref "U2") (pin "K10") (pinfunction "GND_K10") (pintype "power_in"))
      (node (ref "U2") (pin "K12") (pinfunction "GND_K12") (pintype "power_in"))
      (node (ref "U2") (pin "K14") (pinfunction "GND_K14") (pintype "power_in"))
      (node (ref "U2") (pin "L11") (pinfunction "GND_L11") (pintype "power_in"))
      (node (ref "U2") (pin "L13") (pinfunction "GND_L13") (pintype "power_in"))
      (node (ref "U2") (pin "L18") (pinfunction "GND_L18") (pintype "power_in"))
      (node (ref "U2") (pin "L5") (pinfunction "GND_L5") (pintype "power_in"))
      (node (ref "U2") (pin "L9") (pinfunction "GND_L9") (pintype "power_in"))
      (node (ref "U2") (pin "M10") (pinfunction "GND_M10") (pintype "power_in"))
      (node (ref "U2") (pin "M12") (pinfunction "GND_M12") (pintype "power_in"))
      (node (ref "U2") (pin "M14") (pinfunction "GND_M14") (pintype "power_in"))
      (node (ref "U2") (pin "N11") (pinfunction "GND_N11") (pintype "power_in"))
      (node (ref "U2") (pin "N13") (pinfunction "GND_N13") (pintype "power_in"))
      (node (ref "U2") (pin "N15") (pinfunction "SUSPEND_N15") (pintype "input"))
      (node (ref "U2") (pin "N17") (pinfunction "GND_N17") (pintype "power_in"))
      (node (ref "U2") (pin "N2") (pinfunction "GND_N2") (pintype "power_in"))
      (node (ref "U2") (pin "N21") (pinfunction "GND_N21") (pintype "power_in"))
      (node (ref "U2") (pin "N9") (pinfunction "GND_N9") (pintype "power_in"))
      (node (ref "U2") (pin "P10") (pinfunction "GND_P10") (pintype "power_in"))
      (node (ref "U2") (pin "P12") (pinfunction "GND_P12") (pintype "power_in"))
      (node (ref "U2") (pin "P14") (pinfunction "GND_P14") (pintype "power_in"))
      (node (ref "U2") (pin "P15") (pinfunction "RFUSE_P15") (pintype "input"))
      (node (ref "U2") (pin "P16") (pinfunction "VFS_P16") (pintype "input"))
      (node (ref "U2") (pin "R17") (pinfunction "VBATT_R17") (pintype "power_in"))
      (node (ref "U2") (pin "R18") (pinfunction "GND_R18") (pintype "power_in"))
      (node (ref "U2") (pin "R5") (pinfunction "GND_R5") (pintype "power_in"))
      (node (ref "U2") (pin "U2") (pinfunction "GND_U2") (pintype "power_in"))
      (node (ref "U2") (pin "U21") (pinfunction "GND_U21") (pintype "power_in"))
      (node (ref "U2") (pin "U7") (pinfunction "GND_U7") (pintype "power_in"))
      (node (ref "U2") (pin "V10") (pinfunction "GND_V10") (pintype "power_in"))
      (node (ref "U2") (pin "V14") (pinfunction "GND_V14") (pintype "power_in"))
      (node (ref "U2") (pin "V4") (pinfunction "GND_V4") (pintype "power_in"))
      (node (ref "U2") (pin "W16") (pinfunction "GND_W16") (pintype "power_in"))
      (node (ref "U2") (pin "W19") (pinfunction "GND_W19") (pintype "power_in"))
      (node (ref "U2") (pin "W7") (pinfunction "GND_W7") (pintype "power_in"))
      (node (ref "U3") (pin "4") (pinfunction "GND_4") (pintype "power_in"))
      (node (ref "X2") (pin "2") (pinfunction "GND_2") (pintype "passive"))
    )
    (net (code "16") (name "Net-(LD3-C)") (class "Default")
      (node (ref "LD3") (pin "1") (pinfunction "C_1") (pintype "passive"))
      (node (ref "R37") (pin "2") (pinfunction "2_2") (pintype "passive"))
    )
    (net (code "17") (name "Net-(U3-~{H}{slash}~{R})") (class "Default")
      (node (ref "R32") (pin "1") (pinfunction "1_1") (pintype "passive"))
      (node (ref "U3") (pin "7") (pinfunction "~{H}/~{R}_7") (pintype "passive"))
    )
    (net (code "18") (name "Net-(U3-~{WP})") (class "Default")
      (node (ref "R30") (pin "1") (pinfunction "1_1") (pintype "passive"))
      (node (ref "U3") (pin "3") (pinfunction "~{WP}_3") (pintype "passive"))
    )
    (net (code "19") (name "unconnected-(U2E-CMPCS_B_2-PadY20)") (class "Default")
      (node (ref "U2") (pin "Y20") (pinfunction "CMPCS_B_2_Y20") (pintype "input+no_connect"))
    )
    (net (code "20") (name "unconnected-(U2H-NC-PadAB5)") (class "Default")
      (node (ref "U2") (pin "AB5") (pinfunction "NC_AB5") (pintype "passive+no_connect"))
    )
    (net (code "21") (name "unconnected-(U2H-NC-PadE8)") (class "Default")
      (node (ref "U2") (pin "E8") (pinfunction "NC_E8") (pintype "passive+no_connect"))
    )
    (net (code "22") (name "unconnected-(U2H-NC-PadE10)") (class "Default")
      (node (ref "U2") (pin "E10") (pinfunction "NC_E10") (pintype "passive+no_connect"))
    )
    (net (code "23") (name "unconnected-(U2H-NC-PadF8)") (class "Default")
      (node (ref "U2") (pin "F8") (pinfunction "NC_F8") (pintype "passive+no_connect"))
    )
    (net (code "24") (name "unconnected-(U2H-NC-PadF9)") (class "Default")
      (node (ref "U2") (pin "F9") (pinfunction "NC_F9") (pintype "passive+no_connect"))
    )
    (net (code "25") (name "unconnected-(U2H-NC-PadF10)") (class "Default")
      (node (ref "U2") (pin "F10") (pinfunction "NC_F10") (pintype "passive+no_connect"))
    )
    (net (code "26") (name "unconnected-(U2H-NC-PadF12)") (class "Default")
      (node (ref "U2") (pin "F12") (pinfunction "NC_F12") (pintype "passive+no_connect"))
    )
    (net (code "27") (name "unconnected-(U2H-NC-PadG8)") (class "Default")
      (node (ref "U2") (pin "G8") (pinfunction "NC_G8") (pintype "passive+no_connect"))
    )
    (net (code "28") (name "unconnected-(U2H-NC-PadG9)") (class "Default")
      (node (ref "U2") (pin "G9") (pinfunction "NC_G9") (pintype "passive+no_connect"))
    )
    (net (code "29") (name "unconnected-(U2H-NC-PadG11)") (class "Default")
      (node (ref "U2") (pin "G11") (pinfunction "NC_G11") (pintype "passive+no_connect"))
    )
    (net (code "30") (name "unconnected-(U2H-NC-PadH10)") (class "Default")
      (node (ref "U2") (pin "H10") (pinfunction "NC_H10") (pintype "passive+no_connect"))
    )
    (net (code "31") (name "unconnected-(U2H-NC-PadH11)") (class "Default")
      (node (ref "U2") (pin "H11") (pinfunction "NC_H11") (pintype "passive+no_connect"))
    )
    (net (code "32") (name "unconnected-(U2H-NC-PadH12)") (class "Default")
      (node (ref "U2") (pin "H12") (pinfunction "NC_H12") (pintype "passive+no_connect"))
    )
    (net (code "33") (name "unconnected-(U2H-NC-PadR7)") (class "Default")
      (node (ref "U2") (pin "R7") (pinfunction "NC_R7") (pintype "passive+no_connect"))
    )
    (net (code "34") (name "unconnected-(U2H-NC-PadR8)") (class "Default")
      (node (ref "U2") (pin "R8") (pinfunction "NC_R8") (pintype "passive+no_connect"))
    )
    (net (code "35") (name "unconnected-(U2H-NC-PadR9)") (class "Default")
      (node (ref "U2") (pin "R9") (pinfunction "NC_R9") (pintype "passive+no_connect"))
    )
    (net (code "36") (name "unconnected-(U2H-NC-PadR11)") (class "Default")
      (node (ref "U2") (pin "R11") (pinfunction "NC_R11") (pintype "passive+no_connect"))
    )
    (net (code "37") (name "unconnected-(U2H-NC-PadR13)") (class "Default")
      (node (ref "U2") (pin "R13") (pinfunction "NC_R13") (pintype "passive+no_connect"))
    )
    (net (code "38") (name "unconnected-(U2H-NC-PadR15)") (class "Default")
      (node (ref "U2") (pin "R15") (pinfunction "NC_R15") (pintype "passive+no_connect"))
    )
    (net (code "39") (name "unconnected-(U2H-NC-PadR16)") (class "Default")
      (node (ref "U2") (pin "R16") (pinfunction "NC_R16") (pintype "passive+no_connect"))
    )
    (net (code "40") (name "unconnected-(U2H-NC-PadT7)") (class "Default")
      (node (ref "U2") (pin "T7") (pinfunction "NC_T7") (pintype "passive+no_connect"))
    )
    (net (code "41") (name "unconnected-(U2H-NC-PadT8)") (class "Default")
      (node (ref "U2") (pin "T8") (pinfunction "NC_T8") (pintype "passive+no_connect"))
    )
    (net (code "42") (name "unconnected-(U2H-NC-PadT10)") (class "Default")
      (node (ref "U2") (pin "T10") (pinfunction "NC_T10") (pintype "passive+no_connect"))
    )
    (net (code "43") (name "unconnected-(U2H-NC-PadT11)") (class "Default")
      (node (ref "U2") (pin "T11") (pinfunction "NC_T11") (pintype "passive+no_connect"))
    )
    (net (code "44") (name "unconnected-(U2H-NC-PadT12)") (class "Default")
      (node (ref "U2") (pin "T12") (pinfunction "NC_T12") (pintype "passive+no_connect"))
    )
    (net (code "45") (name "unconnected-(U2H-NC-PadT14)") (class "Default")
      (node (ref "U2") (pin "T14") (pinfunction "NC_T14") (pintype "passive+no_connect"))
    )
    (net (code "46") (name "unconnected-(U2H-NC-PadT15)") (class "Default")
      (node (ref "U2") (pin "T15") (pinfunction "NC_T15") (pintype "passive+no_connect"))
    )
    (net (code "47") (name "unconnected-(U2H-NC-PadT16)") (class "Default")
      (node (ref "U2") (pin "T16") (pinfunction "NC_T16") (pintype "passive+no_connect"))
    )
    (net (code "48") (name "unconnected-(U2H-NC-PadU6)") (class "Default")
      (node (ref "U2") (pin "U6") (pinfunction "NC_U6") (pintype "passive+no_connect"))
    )
    (net (code "49") (name "unconnected-(U2H-NC-PadU8)") (class "Default")
      (node (ref "U2") (pin "U8") (pinfunction "NC_U8") (pintype "passive+no_connect"))
    )
    (net (code "50") (name "unconnected-(U2H-NC-PadU9)") (class "Default")
      (node (ref "U2") (pin "U9") (pinfunction "NC_U9") (pintype "passive+no_connect"))
    )
    (net (code "51") (name "unconnected-(U2H-NC-PadU10)") (class "Default")
      (node (ref "U2") (pin "U10") (pinfunction "NC_U10") (pintype "passive+no_connect"))
    )
    (net (code "52") (name "unconnected-(U2H-NC-PadU12)") (class "Default")
      (node (ref "U2") (pin "U12") (pinfunction "NC_U12") (pintype "passive+no_connect"))
    )
    (net (code "53") (name "unconnected-(U2H-NC-PadU16)") (class "Default")
      (node (ref "U2") (pin "U16") (pinfunction "NC_U16") (pintype "passive+no_connect"))
    )
    (net (code "54") (name "unconnected-(U2H-NC-PadU17)") (class "Default")
      (node (ref "U2") (pin "U17") (pinfunction "NC_U17") (pintype "passive+no_connect"))
    )
    (net (code "55") (name "unconnected-(U2H-NC-PadV5)") (class "Default")
      (node (ref "U2") (pin "V5") (pinfunction "NC_V5") (pintype "passive+no_connect"))
    )
    (net (code "56") (name "unconnected-(U2H-NC-PadV7)") (class "Default")
      (node (ref "U2") (pin "V7") (pinfunction "NC_V7") (pintype "passive+no_connect"))
    )
    (net (code "57") (name "unconnected-(U2H-NC-PadV9)") (class "Default")
      (node (ref "U2") (pin "V9") (pinfunction "NC_V9") (pintype "passive+no_connect"))
    )
    (net (code "58") (name "unconnected-(U2H-NC-PadV13)") (class "Default")
      (node (ref "U2") (pin "V13") (pinfunction "NC_V13") (pintype "passive+no_connect"))
    )
    (net (code "59") (name "unconnected-(U2H-NC-PadV17)") (class "Default")
      (node (ref "U2") (pin "V17") (pinfunction "NC_V17") (pintype "passive+no_connect"))
    )
    (net (code "60") (name "unconnected-(U2H-NC-PadV18)") (class "Default")
      (node (ref "U2") (pin "V18") (pinfunction "NC_V18") (pintype "passive+no_connect"))
    )
    (net (code "61") (name "unconnected-(U2H-NC-PadV19)") (class "Default")
      (node (ref "U2") (pin "V19") (pinfunction "NC_V19") (pintype "passive+no_connect"))
    )
    (net (code "62") (name "unconnected-(U2H-NC-PadW6)") (class "Default")
      (node (ref "U2") (pin "W6") (pinfunction "NC_W6") (pintype "passive+no_connect"))
    )
    (net (code "63") (name "unconnected-(U2H-NC-PadW8)") (class "Default")
      (node (ref "U2") (pin "W8") (pinfunction "NC_W8") (pintype "passive+no_connect"))
    )
    (net (code "64") (name "unconnected-(U2H-NC-PadW9)") (class "Default")
      (node (ref "U2") (pin "W9") (pinfunction "NC_W9") (pintype "passive+no_connect"))
    )
    (net (code "65") (name "unconnected-(U2H-NC-PadW10)") (class "Default")
      (node (ref "U2") (pin "W10") (pinfunction "NC_W10") (pintype "passive+no_connect"))
    )
    (net (code "66") (name "unconnected-(U2H-NC-PadW13)") (class "Default")
      (node (ref "U2") (pin "W13") (pinfunction "NC_W13") (pintype "passive+no_connect"))
    )
    (net (code "67") (name "unconnected-(U2H-NC-PadW14)") (class "Default")
      (node (ref "U2") (pin "W14") (pinfunction "NC_W14") (pintype "passive+no_connect"))
    )
    (net (code "68") (name "unconnected-(U2H-NC-PadW15)") (class "Default")
      (node (ref "U2") (pin "W15") (pinfunction "NC_W15") (pintype "passive+no_connect"))
    )
    (net (code "69") (name "unconnected-(U2H-NC-PadW17)") (class "Default")
      (node (ref "U2") (pin "W17") (pinfunction "NC_W17") (pintype "passive+no_connect"))
    )
    (net (code "70") (name "unconnected-(U2H-NC-PadW18)") (class "Default")
      (node (ref "U2") (pin "W18") (pinfunction "NC_W18") (pintype "passive+no_connect"))
    )
    (net (code "71") (name "unconnected-(U2H-NC-PadY5)") (class "Default")
      (node (ref "U2") (pin "Y5") (pinfunction "NC_Y5") (pintype "passive+no_connect"))
    )
    (net (code "72") (name "unconnected-(U2H-NC-PadY6)") (class "Default")
      (node (ref "U2") (pin "Y6") (pinfunction "NC_Y6") (pintype "passive+no_connect"))
    )
    (net (code "73") (name "unconnected-(U2H-NC-PadY8)") (class "Default")
      (node (ref "U2") (pin "Y8") (pinfunction "NC_Y8") (pintype "passive+no_connect"))
    )
    (net (code "74") (name "unconnected-(U2H-NC-PadY10)") (class "Default")
      (node (ref "U2") (pin "Y10") (pinfunction "NC_Y10") (pintype "passive+no_connect"))
    )
    (net (code "75") (name "unconnected-(U2H-NC-PadY14)") (class "Default")
      (node (ref "U2") (pin "Y14") (pinfunction "NC_Y14") (pintype "passive+no_connect"))
    )
    (net (code "76") (name "unconnected-(U2H-NC-PadY16)") (class "Default")
      (node (ref "U2") (pin "Y16") (pinfunction "NC_Y16") (pintype "passive+no_connect"))
    )
    (net (code "77") (name "unconnected-(U2H-NC-PadY18)") (class "Default")
      (node (ref "U2") (pin "Y18") (pinfunction "NC_Y18") (pintype "passive+no_connect"))
    )
  )
)
